# RELAY3.net
KiCad netlist of a schematic drawn in Altium Designer
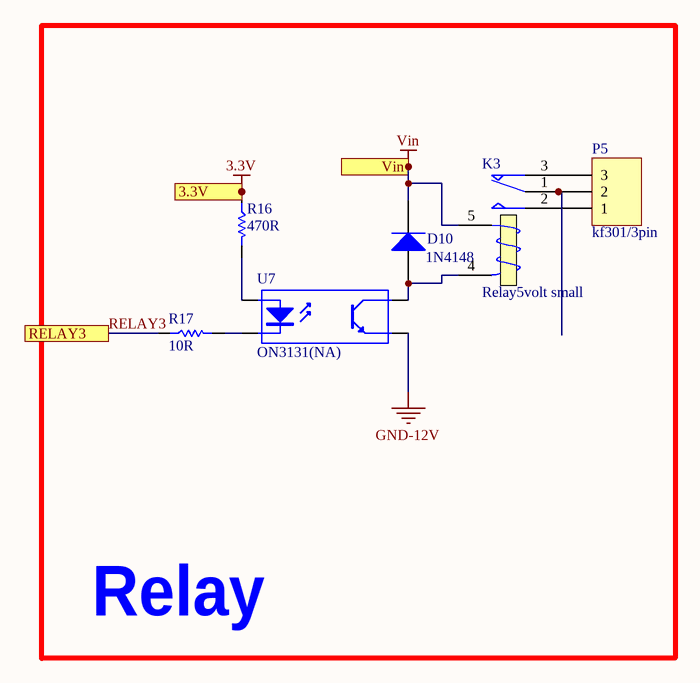
[diagram p0: RELAY3.SchDoc]

(export (version "E")
  (design (tool "Eeschema 10.0.6"))
  (components
    (comp (ref "D10")
      (value "1N4148")
      (footprint "sod123")
      (description "1 Amp General Purpose Rectifier")
      (fields (field (name "PUBLISHER") "Altium Limited"))
      (libsource (lib "Miscellaneous Devices") (part "Diode 1N4007"))
    )
    (comp (ref "K3")
      (value "Relay5volt small")
      (footprint "relay5_childern")
      (description "SPDT Relay")
      (fields (field (name "PUBLISHER") "Altium Limited"))
      (libsource (lib "FLIB") (part "Relay"))
    )
    (comp (ref "P5")
      (value "kf301/3pin")
      (footprint "Blue Connector 1*3 -kf301")
      (fields (field (name "PUBLISHER") "Altium Limited"))
      (libsource (lib "Miscellaneous Connectors") (part "Header 3"))
    )
    (comp (ref "R16")
      (value "470R")
      (footprint "0805/resistor")
      (description "Resistor")
      (fields (field (name "TOLERANCE") "5%") (field (name "POWER") "1/8 W"))
      (libsource (lib "skille") (part "Resistor"))
    )
    (comp (ref "R17")
      (value "10R")
      (footprint "0805/resistor")
      (description "Resistor")
      (fields (field (name "TOLERANCE") "5%") (field (name "POWER") "1/8 W"))
      (libsource (lib "skille") (part "Resistor"))
    )
    (comp (ref "U7")
      (value "ON3131(NA)")
      (footprint "OPTO_COUPLER")
      (description "4-Pin Phototransistor Optocoupler")
      (fields (field (name "PUBLISHER") "Altium Limited"))
      (libsource (lib "skille") (part "Optoisolator1"))
    )
  )
  (nets
    (net (code "1") (name "/RELAY3") (class "Default")
      (node (ref "R17") (pin "1") (pinfunction "1_1") (pintype "passive"))
    )
    (net (code "2") (name "3.3V") (class "Default")
      (node (ref "R16") (pin "1") (pinfunction "1_1") (pintype "passive"))
    )
    (net (code "3") (name "GND-12V") (class "Default")
      (node (ref "U7") (pin "3") (pinfunction "E_3") (pintype "passive"))
    )
    (net (code "4") (name "Net-(K3-COM)") (class "Default")
      (node (ref "K3") (pin "1") (pinfunction "COM_1") (pintype "passive"))
      (node (ref "P5") (pin "2") (pinfunction "2_2") (pintype "passive"))
    )
    (net (code "5") (name "Net-(K3-NO)") (class "Default")
      (node (ref "K3") (pin "2") (pinfunction "NO_2") (pintype "passive"))
      (node (ref "P5") (pin "1") (pinfunction "1_1") (pintype "passive"))
    )
    (net (code "6") (name "Net-(K3-T1)") (class "Default")
      (node (ref "K3") (pin "3") (pinfunction "T1_3") (pintype "passive"))
      (node (ref "P5") (pin "3") (pinfunction "3_3") (pintype "passive"))
    )
    (net (code "7") (name "Net-(K3-T2)") (class "Default")
      (node (ref "D10") (pin "A") (pinfunction "A_A") (pintype "passive"))
      (node (ref "K3") (pin "4") (pinfunction "T2_4") (pintype "passive"))
      (node (ref "U7") (pin "4") (pinfunction "C_4") (pintype "passive"))
    )
    (net (code "8") (name "Net-(U7-A)") (class "Default")
      (node (ref "R16") (pin "2") (pinfunction "2_2") (pintype "passive"))
      (node (ref "U7") (pin "1") (pinfunction "A_1") (pintype "passive"))
    )
    (net (code "9") (name "Net-(U7-K)") (class "Default")
      (node (ref "R17") (pin "2") (pinfunction "2_2") (pintype "passive"))
      (node (ref "U7") (pin "2") (pinfunction "K_2") (pintype "passive"))
    )
    (net (code "10") (name "Vin") (class "Default")
      (node (ref "D10") (pin "K") (pinfunction "K_K") (pintype "passive"))
      (node (ref "K3") (pin "5") (pinfunction "5_5") (pintype "passive"))
    )
  )
)
